# P82B96-I2c-Bus-Extender-V02-005.net
KiCad netlist of a schematic drawn in EAGLE
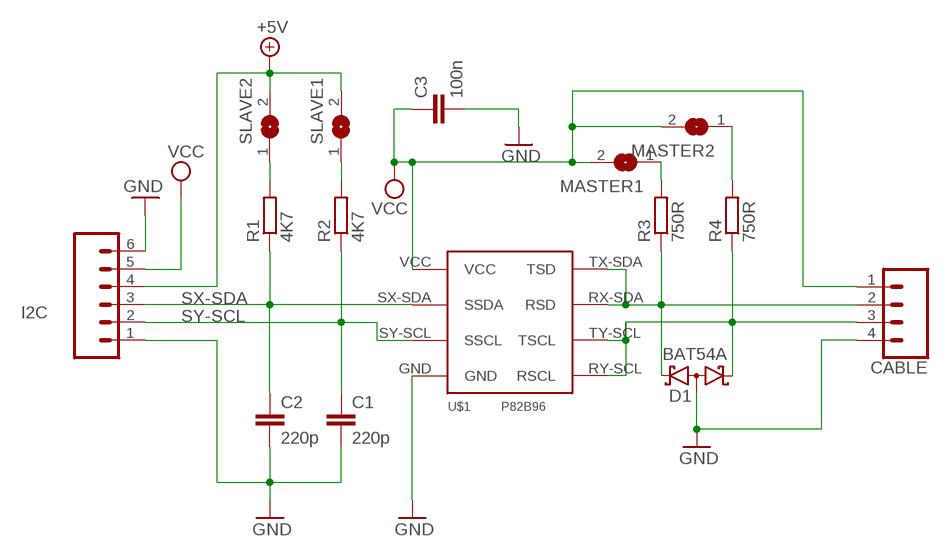
[diagram p0: schematic, sheet 1]

(export (version "E")
  (design (tool "Eeschema 10.0.6"))
  (components
    (comp (ref "C1")
      (value "220p")
      (footprint "eagle-import:C0805K")
      (libsource (lib "eagle-import") (part "C-EUC0805K"))
    )
    (comp (ref "C2")
      (value "220p")
      (footprint "eagle-import:C0805K")
      (libsource (lib "eagle-import") (part "C-EUC0805K"))
    )
    (comp (ref "C3")
      (value "100n")
      (footprint "eagle-import:C0805K")
      (libsource (lib "eagle-import") (part "C-EUC0805K"))
    )
    (comp (ref "CABLE")
      (value "CONN_04LOCK_LONGPADS")
      (footprint "eagle-import:1X04_LOCK_LONGPADS")
      (libsource (lib "eagle-import") (part "CONN_04LOCK_LONGPADS"))
    )
    (comp (ref "D1")
      (value "BAT54A")
      (footprint "eagle-import:SOT23")
      (libsource (lib "eagle-import") (part "BAT54A"))
    )
    (comp (ref "I2C")
      (value "CONN_06LONGPADS")
      (footprint "eagle-import:1X06_LONGPADS")
      (libsource (lib "eagle-import") (part "CONN_06LONGPADS"))
    )
    (comp (ref "MASTER1")
      (value "SJ")
      (footprint "eagle-import:SJ")
      (libsource (lib "eagle-import") (part "SJ"))
    )
    (comp (ref "MASTER2")
      (value "SJ")
      (footprint "eagle-import:SJ")
      (libsource (lib "eagle-import") (part "SJ"))
    )
    (comp (ref "R1")
      (value "4K7")
      (footprint "eagle-import:R0805W")
      (libsource (lib "eagle-import") (part "R-EU_R0805W"))
    )
    (comp (ref "R2")
      (value "4K7")
      (footprint "eagle-import:R0805W")
      (libsource (lib "eagle-import") (part "R-EU_R0805W"))
    )
    (comp (ref "R3")
      (value "750R")
      (footprint "eagle-import:R0805W")
      (libsource (lib "eagle-import") (part "R-EU_R0805W"))
    )
    (comp (ref "R4")
      (value "750R")
      (footprint "eagle-import:R0805W")
      (libsource (lib "eagle-import") (part "R-EU_R0805W"))
    )
    (comp (ref "SLAVE1")
      (value "SJ")
      (footprint "eagle-import:SJ")
      (libsource (lib "eagle-import") (part "SJ"))
    )
    (comp (ref "SLAVE2")
      (value "SJ")
      (footprint "eagle-import:SJ")
      (libsource (lib "eagle-import") (part "SJ"))
    )
    (comp (ref "U$1")
      (value "P82B96-NEW")
      (footprint "eagle-import:SOIC8")
      (libsource (lib "eagle-import") (part "P82B96-NEW"))
    )
  )
  (nets
    (net (code "1") (name "+5V") (class "Default")
      (node (ref "I2C") (pin "4") (pinfunction "4_4") (pintype "passive"))
      (node (ref "SLAVE1") (pin "2") (pinfunction "2_2") (pintype "passive"))
      (node (ref "SLAVE2") (pin "2") (pinfunction "2_2") (pintype "passive"))
    )
    (net (code "2") (name "/SX-SDA") (class "Default")
      (node (ref "C2") (pin "1") (pinfunction "1_1") (pintype "passive"))
      (node (ref "I2C") (pin "3") (pinfunction "3_3") (pintype "passive"))
      (node (ref "R1") (pin "1") (pinfunction "1_1") (pintype "passive"))
      (node (ref "U$1") (pin "SX-SDA") (pinfunction "SSDA_SX-SDA") (pintype "bidirectional"))
    )
    (net (code "3") (name "/SY-SCL") (class "Default")
      (node (ref "C1") (pin "1") (pinfunction "1_1") (pintype "passive"))
      (node (ref "I2C") (pin "2") (pinfunction "2_2") (pintype "passive"))
      (node (ref "R2") (pin "1") (pinfunction "1_1") (pintype "passive"))
      (node (ref "U$1") (pin "SY-SCL") (pinfunction "SSCL_SY-SCL") (pintype "bidirectional"))
    )
    (net (code "4") (name "GND") (class "Default")
      (node (ref "C1") (pin "2") (pinfunction "2_2") (pintype "passive"))
      (node (ref "C2") (pin "2") (pinfunction "2_2") (pintype "passive"))
      (node (ref "C3") (pin "2") (pinfunction "2_2") (pintype "passive"))
      (node (ref "CABLE") (pin "4") (pinfunction "4_4") (pintype "passive"))
      (node (ref "D1") (pin "3") (pinfunction "AA_3") (pintype "passive"))
      (node (ref "I2C") (pin "1") (pinfunction "1_1") (pintype "passive"))
      (node (ref "I2C") (pin "6") (pinfunction "6_6") (pintype "passive"))
      (node (ref "U$1") (pin "GND") (pinfunction "GND_GND") (pintype "bidirectional"))
    )
    (net (code "5") (name "Net-(D1-K1)") (class "Default")
      (node (ref "CABLE") (pin "3") (pinfunction "3_3") (pintype "passive"))
      (node (ref "D1") (pin "1") (pinfunction "K1_1") (pintype "passive"))
      (node (ref "R4") (pin "1") (pinfunction "1_1") (pintype "passive"))
      (node (ref "U$1") (pin "RY-SCL") (pinfunction "RSCL_RY-SCL") (pintype "bidirectional"))
      (node (ref "U$1") (pin "TY-SCL") (pinfunction "TSCL_TY-SCL") (pintype "bidirectional"))
    )
    (net (code "6") (name "Net-(D1-K2)") (class "Default")
      (node (ref "CABLE") (pin "2") (pinfunction "2_2") (pintype "passive"))
      (node (ref "D1") (pin "2") (pinfunction "K2_2") (pintype "passive"))
      (node (ref "R3") (pin "1") (pinfunction "1_1") (pintype "passive"))
      (node (ref "U$1") (pin "RX-SDA") (pinfunction "RSD_RX-SDA") (pintype "bidirectional"))
      (node (ref "U$1") (pin "TX-SDA") (pinfunction "TSD_TX-SDA") (pintype "bidirectional"))
    )
    (net (code "7") (name "Net-(MASTER1-Pad1)") (class "Default")
      (node (ref "MASTER1") (pin "1") (pinfunction "1_1") (pintype "passive"))
      (node (ref "R3") (pin "2") (pinfunction "2_2") (pintype "passive"))
    )
    (net (code "8") (name "Net-(MASTER2-Pad1)") (class "Default")
      (node (ref "MASTER2") (pin "1") (pinfunction "1_1") (pintype "passive"))
      (node (ref "R4") (pin "2") (pinfunction "2_2") (pintype "passive"))
    )
    (net (code "9") (name "Net-(R1-Pad2)") (class "Default")
      (node (ref "R1") (pin "2") (pinfunction "2_2") (pintype "passive"))
      (node (ref "SLAVE2") (pin "1") (pinfunction "1_1") (pintype "passive"))
    )
    (net (code "10") (name "Net-(R2-Pad2)") (class "Default")
      (node (ref "R2") (pin "2") (pinfunction "2_2") (pintype "passive"))
      (node (ref "SLAVE1") (pin "1") (pinfunction "1_1") (pintype "passive"))
    )
    (net (code "11") (name "VCC") (class "Default")
      (node (ref "C3") (pin "1") (pinfunction "1_1") (pintype "passive"))
      (node (ref "CABLE") (pin "1") (pinfunction "1_1") (pintype "passive"))
      (node (ref "I2C") (pin "5") (pinfunction "5_5") (pintype "passive"))
      (node (ref "MASTER1") (pin "2") (pinfunction "2_2") (pintype "passive"))
      (node (ref "MASTER2") (pin "2") (pinfunction "2_2") (pintype "passive"))
      (node (ref "U$1") (pin "VCC") (pinfunction "VCC_VCC") (pintype "bidirectional"))
    )
  )
)
